# gol.net
KiCad netlist of a schematic drawn in EAGLE
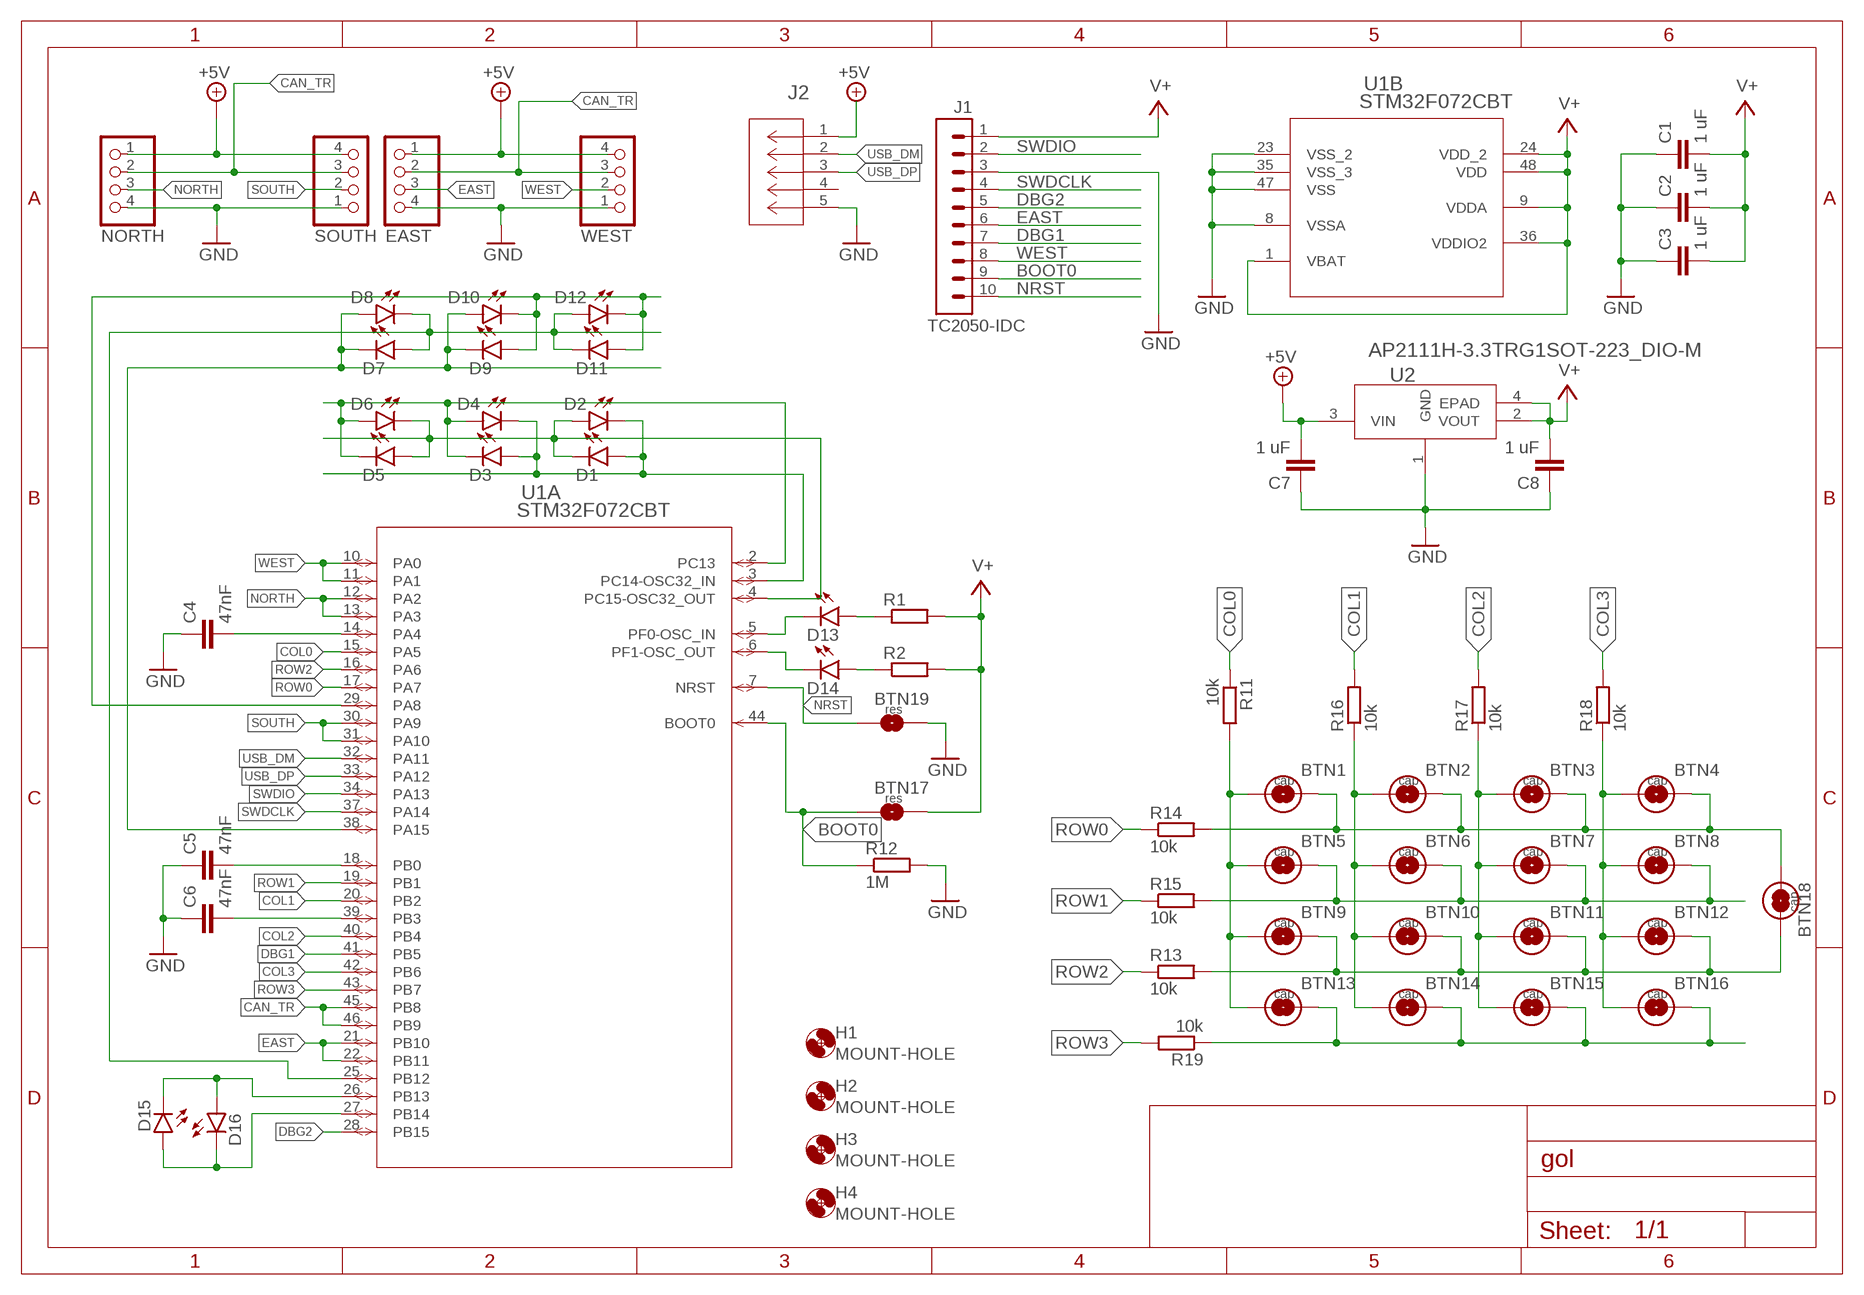
[diagram p0: schematic, sheet 1]

(export (version "E")
  (design (tool "Eeschema 10.0.6"))
  (components
    (comp (ref "BTN1")
      (value "1")
      (footprint "eagle-import:COMB")
      (libsource (lib "eagle-import") (part "BUTTON-CAP"))
    )
    (comp (ref "BTN2")
      (value "2")
      (footprint "eagle-import:COMB")
      (libsource (lib "eagle-import") (part "BUTTON-CAP"))
    )
    (comp (ref "BTN3")
      (value "3")
      (footprint "eagle-import:COMB")
      (libsource (lib "eagle-import") (part "BUTTON-CAP"))
    )
    (comp (ref "BTN4")
      (value "4")
      (footprint "eagle-import:COMB")
      (libsource (lib "eagle-import") (part "BUTTON-CAP"))
    )
    (comp (ref "BTN5")
      (value "5")
      (footprint "eagle-import:COMB")
      (libsource (lib "eagle-import") (part "BUTTON-CAP"))
    )
    (comp (ref "BTN6")
      (value "6")
      (footprint "eagle-import:COMB")
      (libsource (lib "eagle-import") (part "BUTTON-CAP"))
    )
    (comp (ref "BTN7")
      (value "7")
      (footprint "eagle-import:COMB")
      (libsource (lib "eagle-import") (part "BUTTON-CAP"))
    )
    (comp (ref "BTN8")
      (value "8")
      (footprint "eagle-import:COMB")
      (libsource (lib "eagle-import") (part "BUTTON-CAP"))
    )
    (comp (ref "BTN9")
      (value "9")
      (footprint "eagle-import:COMB")
      (libsource (lib "eagle-import") (part "BUTTON-CAP"))
    )
    (comp (ref "BTN10")
      (value "10")
      (footprint "eagle-import:COMB")
      (libsource (lib "eagle-import") (part "BUTTON-CAP"))
    )
    (comp (ref "BTN11")
      (value "11")
      (footprint "eagle-import:COMB")
      (libsource (lib "eagle-import") (part "BUTTON-CAP"))
    )
    (comp (ref "BTN12")
      (value "12")
      (footprint "eagle-import:COMB")
      (libsource (lib "eagle-import") (part "BUTTON-CAP"))
    )
    (comp (ref "BTN13")
      (value "13")
      (footprint "eagle-import:COMB")
      (libsource (lib "eagle-import") (part "BUTTON-CAP"))
    )
    (comp (ref "BTN14")
      (value "14")
      (footprint "eagle-import:COMB")
      (libsource (lib "eagle-import") (part "BUTTON-CAP"))
    )
    (comp (ref "BTN15")
      (value "15")
      (footprint "eagle-import:COMB")
      (libsource (lib "eagle-import") (part "BUTTON-CAP"))
    )
    (comp (ref "BTN16")
      (value "16")
      (footprint "eagle-import:COMB")
      (libsource (lib "eagle-import") (part "BUTTON-CAP"))
    )
    (comp (ref "BTN17")
      (value "FLASH")
      (footprint "eagle-import:COMB_EXPOSED")
      (libsource (lib "eagle-import") (part "BUTTON-RES"))
    )
    (comp (ref "BTN18")
      (value "MENU")
      (footprint "eagle-import:COMB_NARROW")
      (libsource (lib "eagle-import") (part "BUTTON-CAPNARROW"))
    )
    (comp (ref "BTN19")
      (value "RESET")
      (footprint "eagle-import:COMB_EXPOSED")
      (libsource (lib "eagle-import") (part "BUTTON-RES"))
    )
    (comp (ref "C1")
      (value "1 uF")
      (footprint "eagle-import:C0603")
      (libsource (lib "eagle-import") (part "C-EUC0603"))
    )
    (comp (ref "C2")
      (value "1 uF")
      (footprint "eagle-import:C0603")
      (libsource (lib "eagle-import") (part "C-EUC0603"))
    )
    (comp (ref "C3")
      (value "1 uF")
      (footprint "eagle-import:C0603")
      (libsource (lib "eagle-import") (part "C-EUC0603"))
    )
    (comp (ref "C4")
      (value "47nF")
      (footprint "eagle-import:C0603")
      (libsource (lib "eagle-import") (part "C-EUC0603"))
    )
    (comp (ref "C5")
      (value "47nF")
      (footprint "eagle-import:C0603")
      (libsource (lib "eagle-import") (part "C-EUC0603"))
    )
    (comp (ref "C6")
      (value "47nF")
      (footprint "eagle-import:C0603")
      (libsource (lib "eagle-import") (part "C-EUC0603"))
    )
    (comp (ref "C7")
      (value "1 uF")
      (footprint "eagle-import:C0603")
      (libsource (lib "eagle-import") (part "C-EUC0603"))
    )
    (comp (ref "C8")
      (value "1 uF")
      (footprint "eagle-import:C0603")
      (libsource (lib "eagle-import") (part "C-EUC0603"))
    )
    (comp (ref "D1")
      (value "LED-5MM")
      (footprint "eagle-import:LED5MM")
      (libsource (lib "eagle-import") (part "LED-5MM"))
    )
    (comp (ref "D2")
      (value "LED-5MM")
      (footprint "eagle-import:LED5MM")
      (libsource (lib "eagle-import") (part "LED-5MM"))
    )
    (comp (ref "D3")
      (value "LED-5MM")
      (footprint "eagle-import:LED5MM")
      (libsource (lib "eagle-import") (part "LED-5MM"))
    )
    (comp (ref "D4")
      (value "LED-5MM")
      (footprint "eagle-import:LED5MM")
      (libsource (lib "eagle-import") (part "LED-5MM"))
    )
    (comp (ref "D5")
      (value "LED-5MM")
      (footprint "eagle-import:LED5MM")
      (libsource (lib "eagle-import") (part "LED-5MM"))
    )
    (comp (ref "D6")
      (value "LED-5MM")
      (footprint "eagle-import:LED5MM")
      (libsource (lib "eagle-import") (part "LED-5MM"))
    )
    (comp (ref "D7")
      (value "LED-5MM")
      (footprint "eagle-import:LED5MM")
      (libsource (lib "eagle-import") (part "LED-5MM"))
    )
    (comp (ref "D8")
      (value "LED-5MM")
      (footprint "eagle-import:LED5MM")
      (libsource (lib "eagle-import") (part "LED-5MM"))
    )
    (comp (ref "D9")
      (value "LED-5MM")
      (footprint "eagle-import:LED5MM")
      (libsource (lib "eagle-import") (part "LED-5MM"))
    )
    (comp (ref "D10")
      (value "LED-5MM")
      (footprint "eagle-import:LED5MM")
      (libsource (lib "eagle-import") (part "LED-5MM"))
    )
    (comp (ref "D11")
      (value "LED-5MM")
      (footprint "eagle-import:LED5MM")
      (libsource (lib "eagle-import") (part "LED-5MM"))
    )
    (comp (ref "D12")
      (value "LED-5MM")
      (footprint "eagle-import:LED5MM")
      (libsource (lib "eagle-import") (part "LED-5MM"))
    )
    (comp (ref "D13")
      (value "LED-5MM")
      (footprint "eagle-import:LED5MM")
      (libsource (lib "eagle-import") (part "LED-5MM"))
    )
    (comp (ref "D14")
      (value "LED-5MM")
      (footprint "eagle-import:LED5MM")
      (libsource (lib "eagle-import") (part "LED-5MM"))
    )
    (comp (ref "D15")
      (value "LED-5MM")
      (footprint "eagle-import:LED5MM")
      (libsource (lib "eagle-import") (part "LED-5MM"))
    )
    (comp (ref "D16")
      (value "LED-5MM")
      (footprint "eagle-import:LED5MM")
      (libsource (lib "eagle-import") (part "LED-5MM"))
    )
    (comp (ref "EAST")
      (value "EAST")
      (footprint "eagle-import:1X04")
      (libsource (lib "eagle-import") (part "PINHD-1X04"))
    )
    (comp (ref "H1")
      (value "MOUNT-HOLE")
      (footprint "eagle-import:MOUNT-HOLE-2,8")
      (libsource (lib "eagle-import") (part "MOUNT-HOLE"))
    )
    (comp (ref "H2")
      (value "MOUNT-HOLE")
      (footprint "eagle-import:MOUNT-HOLE-2,8")
      (libsource (lib "eagle-import") (part "MOUNT-HOLE"))
    )
    (comp (ref "H3")
      (value "MOUNT-HOLE")
      (footprint "eagle-import:MOUNT-HOLE-2,8")
      (libsource (lib "eagle-import") (part "MOUNT-HOLE"))
    )
    (comp (ref "H4")
      (value "MOUNT-HOLE")
      (footprint "eagle-import:MOUNT-HOLE-2,8")
      (libsource (lib "eagle-import") (part "MOUNT-HOLE"))
    )
    (comp (ref "J1")
      (value "TC2050-IDC")
      (footprint "eagle-import:TC2050-IDC")
      (libsource (lib "eagle-import") (part "TC2050-IDC"))
    )
    (comp (ref "J2")
      (value "2057-MCR-B-S-RA-TSMT-NP-CS4-T/RCT-ND")
      (footprint "eagle-import:CONN_10118192-0002LF_AMP")
      (fields
        (field (name "MANUFACTURER_PART_NUMBER") "10118192-0002LF")
        (field (name "COPYRIGHT") "Copyright (C) 2023 Ultra Librarian. All rights reserved.")
      )
      (libsource (lib "eagle-import") (part "10118192-0002LFCONN_10118192-0002LF_AMP"))
    )
    (comp (ref "NORTH")
      (value "NORTH")
      (footprint "eagle-import:JP4-RA-FEM")
      (libsource (lib "eagle-import") (part "PINHD-1X041X04-RA-FEM"))
    )
    (comp (ref "R1")
      (value "R-EU-0207/8")
      (footprint "eagle-import:0207_8")
      (libsource (lib "eagle-import") (part "R-EU-0207/8"))
    )
    (comp (ref "R2")
      (value "R-EU-0207/8")
      (footprint "eagle-import:0207_8")
      (libsource (lib "eagle-import") (part "R-EU-0207/8"))
    )
    (comp (ref "R11")
      (value "10k")
      (footprint "eagle-import:R0603")
      (libsource (lib "eagle-import") (part "R-EU_R0603"))
    )
    (comp (ref "R12")
      (value "1M")
      (footprint "eagle-import:R0603")
      (libsource (lib "eagle-import") (part "R-EU_R0603"))
    )
    (comp (ref "R13")
      (value "10k")
      (footprint "eagle-import:R0603")
      (libsource (lib "eagle-import") (part "R-EU_R0603"))
    )
    (comp (ref "R14")
      (value "10k")
      (footprint "eagle-import:R0603")
      (libsource (lib "eagle-import") (part "R-EU_R0603"))
    )
    (comp (ref "R15")
      (value "10k")
      (footprint "eagle-import:R0603")
      (libsource (lib "eagle-import") (part "R-EU_R0603"))
    )
    (comp (ref "R16")
      (value "10k")
      (footprint "eagle-import:R0603")
      (libsource (lib "eagle-import") (part "R-EU_R0603"))
    )
    (comp (ref "R17")
      (value "10k")
      (footprint "eagle-import:R0603")
      (libsource (lib "eagle-import") (part "R-EU_R0603"))
    )
    (comp (ref "R18")
      (value "10k")
      (footprint "eagle-import:R0603")
      (libsource (lib "eagle-import") (part "R-EU_R0603"))
    )
    (comp (ref "R19")
      (value "10k")
      (footprint "eagle-import:R0603")
      (libsource (lib "eagle-import") (part "R-EU_R0603"))
    )
    (comp (ref "SOUTH")
      (value "SOUTH")
      (footprint "eagle-import:1X04_90")
      (libsource (lib "eagle-import") (part "PINHD-1X4/90"))
    )
    (comp (ref "U1")
      (value "STM32F072CBT")
      (footprint "eagle-import:LQFP48-7X7MM")
      (fields
        (field (name "MANUFACTURER_PART_NUMBER") "STM32F072CBT6")
        (field (name "COPYRIGHT") "Copyright (C) 2023 Ultra Librarian. All rights reserved.")
      )
      (libsource (lib "eagle-import") (part "STM32F072CBT6LQFP48-7X7MM"))
    )
    (comp (ref "U2")
      (value "AP2111H-3.3TRG1SOT-223_DIO-M")
      (footprint "eagle-import:SOT-223_DIO-M")
      (fields
        (field (name "MANUFACTURER_PART_NUMBER") "AP2111H-3.3TRG1")
        (field (name "COPYRIGHT") "Copyright (C) 2023 Ultra Librarian. All rights reserved.")
      )
      (libsource (lib "eagle-import") (part "AP2111H-3.3TRG1SOT-223_DIO-M"))
    )
    (comp (ref "WEST")
      (value "WEST")
      (footprint "eagle-import:1X04")
      (libsource (lib "eagle-import") (part "PINHD-1X04"))
    )
  )
  (nets
    (net (code "1") (name "+5V") (class "Default")
      (node (ref "C7") (pin "2") (pinfunction "2_2") (pintype "passive"))
      (node (ref "EAST") (pin "1") (pinfunction "1_1") (pintype "passive"))
      (node (ref "J2") (pin "1") (pinfunction "1_1") (pintype "passive"))
      (node (ref "NORTH") (pin "1") (pinfunction "1_1") (pintype "passive"))
      (node (ref "SOUTH") (pin "4") (pinfunction "4_4") (pintype "passive"))
      (node (ref "U2") (pin "3") (pinfunction "VIN_3") (pintype "input"))
      (node (ref "WEST") (pin "4") (pinfunction "4_4") (pintype "passive"))
    )
    (net (code "2") (name "BOOT0") (class "Default")
      (node (ref "BTN17") (pin "P$1") (pinfunction "1_P$1") (pintype "passive"))
      (node (ref "J1") (pin "9") (pinfunction "9_9") (pintype "passive"))
      (node (ref "R12") (pin "1") (pinfunction "1_1") (pintype "passive"))
      (node (ref "U1") (pin "44") (pinfunction "BOOT0_44") (pintype "input"))
    )
    (net (code "3") (name "CAN_TR") (class "Default")
      (node (ref "EAST") (pin "2") (pinfunction "2_2") (pintype "passive"))
      (node (ref "NORTH") (pin "2") (pinfunction "2_2") (pintype "passive"))
      (node (ref "SOUTH") (pin "3") (pinfunction "3_3") (pintype "passive"))
      (node (ref "U1") (pin "45") (pinfunction "PB8_45") (pintype "bidirectional"))
      (node (ref "U1") (pin "46") (pinfunction "PB9_46") (pintype "bidirectional"))
      (node (ref "WEST") (pin "3") (pinfunction "3_3") (pintype "passive"))
    )
    (net (code "4") (name "COL0") (class "Default")
      (node (ref "R11") (pin "1") (pinfunction "1_1") (pintype "passive"))
      (node (ref "U1") (pin "15") (pinfunction "PA5_15") (pintype "bidirectional"))
    )
    (net (code "5") (name "COL1") (class "Default")
      (node (ref "R16") (pin "2") (pinfunction "2_2") (pintype "passive"))
      (node (ref "U1") (pin "20") (pinfunction "PB2_20") (pintype "bidirectional"))
    )
    (net (code "6") (name "COL2") (class "Default")
      (node (ref "R17") (pin "2") (pinfunction "2_2") (pintype "passive"))
      (node (ref "U1") (pin "40") (pinfunction "PB4_40") (pintype "bidirectional"))
    )
    (net (code "7") (name "COL3") (class "Default")
      (node (ref "R18") (pin "2") (pinfunction "2_2") (pintype "passive"))
      (node (ref "U1") (pin "42") (pinfunction "PB6_42") (pintype "bidirectional"))
    )
    (net (code "8") (name "DBG1") (class "Default")
      (node (ref "J1") (pin "7") (pinfunction "7_7") (pintype "passive"))
      (node (ref "U1") (pin "41") (pinfunction "PB5_41") (pintype "bidirectional"))
    )
    (net (code "9") (name "DBG2") (class "Default")
      (node (ref "J1") (pin "5") (pinfunction "5_5") (pintype "passive"))
      (node (ref "U1") (pin "28") (pinfunction "PB15_28") (pintype "bidirectional"))
    )
    (net (code "10") (name "EAST") (class "Default")
      (node (ref "EAST") (pin "3") (pinfunction "3_3") (pintype "passive"))
      (node (ref "J1") (pin "6") (pinfunction "6_6") (pintype "passive"))
      (node (ref "U1") (pin "21") (pinfunction "PB10_21") (pintype "bidirectional"))
      (node (ref "U1") (pin "22") (pinfunction "PB11_22") (pintype "bidirectional"))
    )
    (net (code "11") (name "GND") (class "Default")
      (node (ref "BTN19") (pin "P$2") (pinfunction "2_P$2") (pintype "passive"))
      (node (ref "C1") (pin "1") (pinfunction "1_1") (pintype "passive"))
      (node (ref "C2") (pin "1") (pinfunction "1_1") (pintype "passive"))
      (node (ref "C3") (pin "1") (pinfunction "1_1") (pintype "passive"))
      (node (ref "C4") (pin "1") (pinfunction "1_1") (pintype "passive"))
      (node (ref "C5") (pin "1") (pinfunction "1_1") (pintype "passive"))
      (node (ref "C6") (pin "1") (pinfunction "1_1") (pintype "passive"))
      (node (ref "C7") (pin "1") (pinfunction "1_1") (pintype "passive"))
      (node (ref "C8") (pin "1") (pinfunction "1_1") (pintype "passive"))
      (node (ref "EAST") (pin "4") (pinfunction "4_4") (pintype "passive"))
      (node (ref "J1") (pin "3") (pinfunction "3_3") (pintype "passive"))
      (node (ref "J2") (pin "5") (pinfunction "5_5") (pintype "passive"))
      (node (ref "NORTH") (pin "4") (pinfunction "4_4") (pintype "passive"))
      (node (ref "R12") (pin "2") (pinfunction "2_2") (pintype "passive"))
      (node (ref "SOUTH") (pin "1") (pinfunction "1_1") (pintype "passive"))
      (node (ref "U1") (pin "23") (pinfunction "VSS_2_23") (pintype "power_in"))
      (node (ref "U1") (pin "35") (pinfunction "VSS_3_35") (pintype "power_in"))
      (node (ref "U1") (pin "47") (pinfunction "VSS_47") (pintype "power_in"))
      (node (ref "U1") (pin "8") (pinfunction "VSSA_8") (pintype "power_in"))
      (node (ref "U2") (pin "1") (pinfunction "GND_1") (pintype "power_in"))
      (node (ref "WEST") (pin "1") (pinfunction "1_1") (pintype "passive"))
    )
    (net (code "12") (name "NORTH") (class "Default")
      (node (ref "NORTH") (pin "3") (pinfunction "3_3") (pintype "passive"))
      (node (ref "U1") (pin "12") (pinfunction "PA2_12") (pintype "bidirectional"))
      (node (ref "U1") (pin "13") (pinfunction "PA3_13") (pintype "bidirectional"))
    )
    (net (code "13") (name "NRST") (class "Default")
      (node (ref "BTN19") (pin "P$1") (pinfunction "1_P$1") (pintype "passive"))
      (node (ref "J1") (pin "10") (pinfunction "10_10") (pintype "passive"))
      (node (ref "U1") (pin "7") (pinfunction "NRST_7") (pintype "bidirectional"))
    )
    (net (code "14") (name "Net-(BTN1-1)") (class "Default")
      (node (ref "BTN1") (pin "P$1") (pinfunction "1_P$1") (pintype "passive"))
      (node (ref "BTN13") (pin "P$1") (pinfunction "1_P$1") (pintype "passive"))
      (node (ref "BTN5") (pin "P$1") (pinfunction "1_P$1") (pintype "passive"))
      (node (ref "BTN9") (pin "P$1") (pinfunction "1_P$1") (pintype "passive"))
      (node (ref "R11") (pin "2") (pinfunction "2_2") (pintype "passive"))
    )
    (net (code "15") (name "Net-(BTN1-2)") (class "Default")
      (node (ref "BTN1") (pin "P$2") (pinfunction "2_P$2") (pintype "passive"))
      (node (ref "BTN18") (pin "P$1") (pinfunction "1_P$1") (pintype "passive"))
      (node (ref "BTN2") (pin "P$2") (pinfunction "2_P$2") (pintype "passive"))
      (node (ref "BTN3") (pin "P$2") (pinfunction "2_P$2") (pintype "passive"))
      (node (ref "BTN4") (pin "P$2") (pinfunction "2_P$2") (pintype "passive"))
      (node (ref "R14") (pin "2") (pinfunction "2_2") (pintype "passive"))
    )
    (net (code "16") (name "Net-(BTN5-2)") (class "Default")
      (node (ref "BTN5") (pin "P$2") (pinfunction "2_P$2") (pintype "passive"))
      (node (ref "BTN6") (pin "P$2") (pinfunction "2_P$2") (pintype "passive"))
      (node (ref "BTN7") (pin "P$2") (pinfunction "2_P$2") (pintype "passive"))
      (node (ref "BTN8") (pin "P$2") (pinfunction "2_P$2") (pintype "passive"))
      (node (ref "R15") (pin "2") (pinfunction "2_2") (pintype "passive"))
    )
    (net (code "17") (name "Net-(BTN10-1)") (class "Default")
      (node (ref "BTN10") (pin "P$1") (pinfunction "1_P$1") (pintype "passive"))
      (node (ref "BTN14") (pin "P$1") (pinfunction "1_P$1") (pintype "passive"))
      (node (ref "BTN2") (pin "P$1") (pinfunction "1_P$1") (pintype "passive"))
      (node (ref "BTN6") (pin "P$1") (pinfunction "1_P$1") (pintype "passive"))
      (node (ref "R16") (pin "1") (pinfunction "1_1") (pintype "passive"))
    )
    (net (code "18") (name "Net-(BTN10-2)") (class "Default")
      (node (ref "BTN10") (pin "P$2") (pinfunction "2_P$2") (pintype "passive"))
      (node (ref "BTN11") (pin "P$2") (pinfunction "2_P$2") (pintype "passive"))
      (node (ref "BTN12") (pin "P$2") (pinfunction "2_P$2") (pintype "passive"))
      (node (ref "BTN18") (pin "P$2") (pinfunction "2_P$2") (pintype "passive"))
      (node (ref "BTN9") (pin "P$2") (pinfunction "2_P$2") (pintype "passive"))
      (node (ref "R13") (pin "2") (pinfunction "2_2") (pintype "passive"))
    )
    (net (code "19") (name "Net-(BTN11-1)") (class "Default")
      (node (ref "BTN11") (pin "P$1") (pinfunction "1_P$1") (pintype "passive"))
      (node (ref "BTN15") (pin "P$1") (pinfunction "1_P$1") (pintype "passive"))
      (node (ref "BTN3") (pin "P$1") (pinfunction "1_P$1") (pintype "passive"))
      (node (ref "BTN7") (pin "P$1") (pinfunction "1_P$1") (pintype "passive"))
      (node (ref "R17") (pin "1") (pinfunction "1_1") (pintype "passive"))
    )
    (net (code "20") (name "Net-(BTN12-1)") (class "Default")
      (node (ref "BTN12") (pin "P$1") (pinfunction "1_P$1") (pintype "passive"))
      (node (ref "BTN16") (pin "P$1") (pinfunction "1_P$1") (pintype "passive"))
      (node (ref "BTN4") (pin "P$1") (pinfunction "1_P$1") (pintype "passive"))
      (node (ref "BTN8") (pin "P$1") (pinfunction "1_P$1") (pintype "passive"))
      (node (ref "R18") (pin "1") (pinfunction "1_1") (pintype "passive"))
    )
    (net (code "21") (name "Net-(BTN13-2)") (class "Default")
      (node (ref "BTN13") (pin "P$2") (pinfunction "2_P$2") (pintype "passive"))
      (node (ref "BTN14") (pin "P$2") (pinfunction "2_P$2") (pintype "passive"))
      (node (ref "BTN15") (pin "P$2") (pinfunction "2_P$2") (pintype "passive"))
      (node (ref "BTN16") (pin "P$2") (pinfunction "2_P$2") (pintype "passive"))
      (node (ref "R19") (pin "1") (pinfunction "1_1") (pintype "passive"))
    )
    (net (code "22") (name "Net-(D1-C)") (class "Default")
      (node (ref "D1") (pin "K") (pinfunction "C_K") (pintype "passive"))
      (node (ref "D2") (pin "A") (pinfunction "A_A") (pintype "passive"))
      (node (ref "D5") (pin "A") (pinfunction "A_A") (pintype "passive"))
      (node (ref "D6") (pin "K") (pinfunction "C_K") (pintype "passive"))
      (node (ref "U1") (pin "4") (pinfunction "PC15-OSC32_OUT_4") (pintype "bidirectional"))
    )
    (net (code "23") (name "Net-(D2-C)") (class "Default")
      (node (ref "D1") (pin "A") (pinfunction "A_A") (pintype "passive"))
      (node (ref "D2") (pin "K") (pinfunction "C_K") (pintype "passive"))
      (node (ref "D3") (pin "A") (pinfunction "A_A") (pintype "passive"))
      (node (ref "D4") (pin "K") (pinfunction "C_K") (pintype "passive"))
      (node (ref "U1") (pin "3") (pinfunction "PC14-OSC32_IN_3") (pintype "bidirectional"))
    )
    (net (code "24") (name "Net-(D3-C)") (class "Default")
      (node (ref "D3") (pin "K") (pinfunction "C_K") (pintype "passive"))
      (node (ref "D4") (pin "A") (pinfunction "A_A") (pintype "passive"))
      (node (ref "D5") (pin "K") (pinfunction "C_K") (pintype "passive"))
      (node (ref "D6") (pin "A") (pinfunction "A_A") (pintype "passive"))
      (node (ref "U1") (pin "2") (pinfunction "PC13_2") (pintype "bidirectional"))
    )
    (net (code "25") (name "Net-(D7-C)") (class "Default")
      (node (ref "D10") (pin "A") (pinfunction "A_A") (pintype "passive"))
      (node (ref "D7") (pin "K") (pinfunction "C_K") (pintype "passive"))
      (node (ref "D8") (pin "A") (pinfunction "A_A") (pintype "passive"))
      (node (ref "D9") (pin "K") (pinfunction "C_K") (pintype "passive"))
      (node (ref "U1") (pin "38") (pinfunction "PA15_38") (pintype "bidirectional"))
    )
    (net (code "26") (name "Net-(D10-C)") (class "Default")
      (node (ref "D10") (pin "K") (pinfunction "C_K") (pintype "passive"))
      (node (ref "D11") (pin "A") (pinfunction "A_A") (pintype "passive"))
      (node (ref "D12") (pin "K") (pinfunction "C_K") (pintype "passive"))
      (node (ref "D9") (pin "A") (pinfunction "A_A") (pintype "passive"))
      (node (ref "U1") (pin "29") (pinfunction "PA8_29") (pintype "bidirectional"))
    )
    (net (code "27") (name "Net-(D11-C)") (class "Default")
      (node (ref "D11") (pin "K") (pinfunction "C_K") (pintype "passive"))
      (node (ref "D12") (pin "A") (pinfunction "A_A") (pintype "passive"))
      (node (ref "D7") (pin "A") (pinfunction "A_A") (pintype "passive"))
      (node (ref "D8") (pin "K") (pinfunction "C_K") (pintype "passive"))
      (node (ref "U1") (pin "25") (pinfunction "PB12_25") (pintype "bidirectional"))
    )
    (net (code "28") (name "Net-(D13-C)") (class "Default")
      (node (ref "D13") (pin "K") (pinfunction "C_K") (pintype "passive"))
      (node (ref "U1") (pin "5") (pinfunction "PF0-OSC_IN_5") (pintype "bidirectional"))
    )
    (net (code "29") (name "Net-(D13-PadA)") (class "Default")
      (node (ref "D13") (pin "A") (pinfunction "A_A") (pintype "passive"))
      (node (ref "R1") (pin "1") (pinfunction "1_1") (pintype "passive"))
    )
    (net (code "30") (name "Net-(D14-C)") (class "Default")
      (node (ref "D14") (pin "K") (pinfunction "C_K") (pintype "passive"))
      (node (ref "U1") (pin "6") (pinfunction "PF1-OSC_OUT_6") (pintype "bidirectional"))
    )
    (net (code "31") (name "Net-(D14-PadA)") (class "Default")
      (node (ref "D14") (pin "A") (pinfunction "A_A") (pintype "passive"))
      (node (ref "R2") (pin "1") (pinfunction "1_1") (pintype "passive"))
    )
    (net (code "32") (name "Net-(D15-C)") (class "Default")
      (node (ref "D15") (pin "K") (pinfunction "C_K") (pintype "passive"))
      (node (ref "D16") (pin "A") (pinfunction "A_A") (pintype "passive"))
      (node (ref "U1") (pin "26") (pinfunction "PB13_26") (pintype "bidirectional"))
    )
    (net (code "33") (name "Net-(D16-C)") (class "Default")
      (node (ref "D15") (pin "A") (pinfunction "A_A") (pintype "passive"))
      (node (ref "D16") (pin "K") (pinfunction "C_K") (pintype "passive"))
      (node (ref "U1") (pin "27") (pinfunction "PB14_27") (pintype "bidirectional"))
    )
    (net (code "34") (name "Net-(U1A-PA4)") (class "Default")
      (node (ref "C4") (pin "2") (pinfunction "2_2") (pintype "passive"))
      (node (ref "U1") (pin "14") (pinfunction "PA4_14") (pintype "bidirectional"))
    )
    (net (code "35") (name "Net-(U1A-PB0)") (class "Default")
      (node (ref "C5") (pin "2") (pinfunction "2_2") (pintype "passive"))
      (node (ref "U1") (pin "18") (pinfunction "PB0_18") (pintype "bidirectional"))
    )
    (net (code "36") (name "Net-(U1A-PB3)") (class "Default")
      (node (ref "C6") (pin "2") (pinfunction "2_2") (pintype "passive"))
      (node (ref "U1") (pin "39") (pinfunction "PB3_39") (pintype "bidirectional"))
    )
    (net (code "37") (name "ROW0") (class "Default")
      (node (ref "R14") (pin "1") (pinfunction "1_1") (pintype "passive"))
      (node (ref "U1") (pin "17") (pinfunction "PA7_17") (pintype "bidirectional"))
    )
    (net (code "38") (name "ROW1") (class "Default")
      (node (ref "R15") (pin "1") (pinfunction "1_1") (pintype "passive"))
      (node (ref "U1") (pin "19") (pinfunction "PB1_19") (pintype "bidirectional"))
    )
    (net (code "39") (name "ROW2") (class "Default")
      (node (ref "R13") (pin "1") (pinfunction "1_1") (pintype "passive"))
      (node (ref "U1") (pin "16") (pinfunction "PA6_16") (pintype "bidirectional"))
    )
    (net (code "40") (name "ROW3") (class "Default")
      (node (ref "R19") (pin "2") (pinfunction "2_2") (pintype "passive"))
      (node (ref "U1") (pin "43") (pinfunction "PB7_43") (pintype "bidirectional"))
    )
    (net (code "41") (name "SOUTH") (class "Default")
      (node (ref "SOUTH") (pin "2") (pinfunction "2_2") (pintype "passive"))
      (node (ref "U1") (pin "30") (pinfunction "PA9_30") (pintype "bidirectional"))
      (node (ref "U1") (pin "31") (pinfunction "PA10_31") (pintype "bidirectional"))
    )
    (net (code "42") (name "SWDCLK") (class "Default")
      (node (ref "J1") (pin "4") (pinfunction "4_4") (pintype "passive"))
      (node (ref "U1") (pin "37") (pinfunction "PA14_37") (pintype "bidirectional"))
    )
    (net (code "43") (name "SWDIO") (class "Default")
      (node (ref "J1") (pin "2") (pinfunction "2_2") (pintype "passive"))
      (node (ref "U1") (pin "34") (pinfunction "PA13_34") (pintype "bidirectional"))
    )
    (net (code "44") (name "USB_DM") (class "Default")
      (node (ref "J2") (pin "2") (pinfunction "2_2") (pintype "passive"))
      (node (ref "U1") (pin "32") (pinfunction "PA11_32") (pintype "bidirectional"))
    )
    (net (code "45") (name "USB_DP") (class "Default")
      (node (ref "J2") (pin "3") (pinfunction "3_3") (pintype "passive"))
      (node (ref "U1") (pin "33") (pinfunction "PA12_33") (pintype "bidirectional"))
    )
    (net (code "46") (name "V+") (class "Default")
      (node (ref "BTN17") (pin "P$2") (pinfunction "2_P$2") (pintype "passive"))
      (node (ref "C1") (pin "2") (pinfunction "2_2") (pintype "passive"))
      (node (ref "C2") (pin "2") (pinfunction "2_2") (pintype "passive"))
      (node (ref "C3") (pin "2") (pinfunction "2_2") (pintype "passive"))
      (node (ref "C8") (pin "2") (pinfunction "2_2") (pintype "passive"))
      (node (ref "J1") (pin "1") (pinfunction "1_1") (pintype "passive"))
      (node (ref "R1") (pin "2") (pinfunction "2_2") (pintype "passive"))
      (node (ref "R2") (pin "2") (pinfunction "2_2") (pintype "passive"))
      (node (ref "U1") (pin "1") (pinfunction "VBAT_1") (pintype "power_in"))
      (node (ref "U1") (pin "24") (pinfunction "VDD_2_24") (pintype "power_in"))
      (node (ref "U1") (pin "36") (pinfunction "VDDIO2_36") (pintype "power_in"))
      (node (ref "U1") (pin "48") (pinfunction "VDD_48") (pintype "power_in"))
      (node (ref "U1") (pin "9") (pinfunction "VDDA_9") (pintype "power_in"))
      (node (ref "U2") (pin "2") (pinfunction "VOUT_2") (pintype "output"))
      (node (ref "U2") (pin "4") (pinfunction "EPAD_4") (pintype "passive"))
    )
    (net (code "47") (name "WEST") (class "Default")
      (node (ref "J1") (pin "8") (pinfunction "8_8") (pintype "passive"))
      (node (ref "U1") (pin "10") (pinfunction "PA0_10") (pintype "bidirectional"))
      (node (ref "U1") (pin "11") (pinfunction "PA1_11") (pintype "bidirectional"))
      (node (ref "WEST") (pin "2") (pinfunction "2_2") (pintype "passive"))
    )
    (net (code "48") (name "unconnected-(J2-Pad4)") (class "Default")
      (node (ref "J2") (pin "4") (pinfunction "4_4") (pintype "passive"))
    )
  )
)
